# Scheda_ufficiale_2020_team_SPQR_3.net
KiCad netlist of a schematic drawn in EAGLE
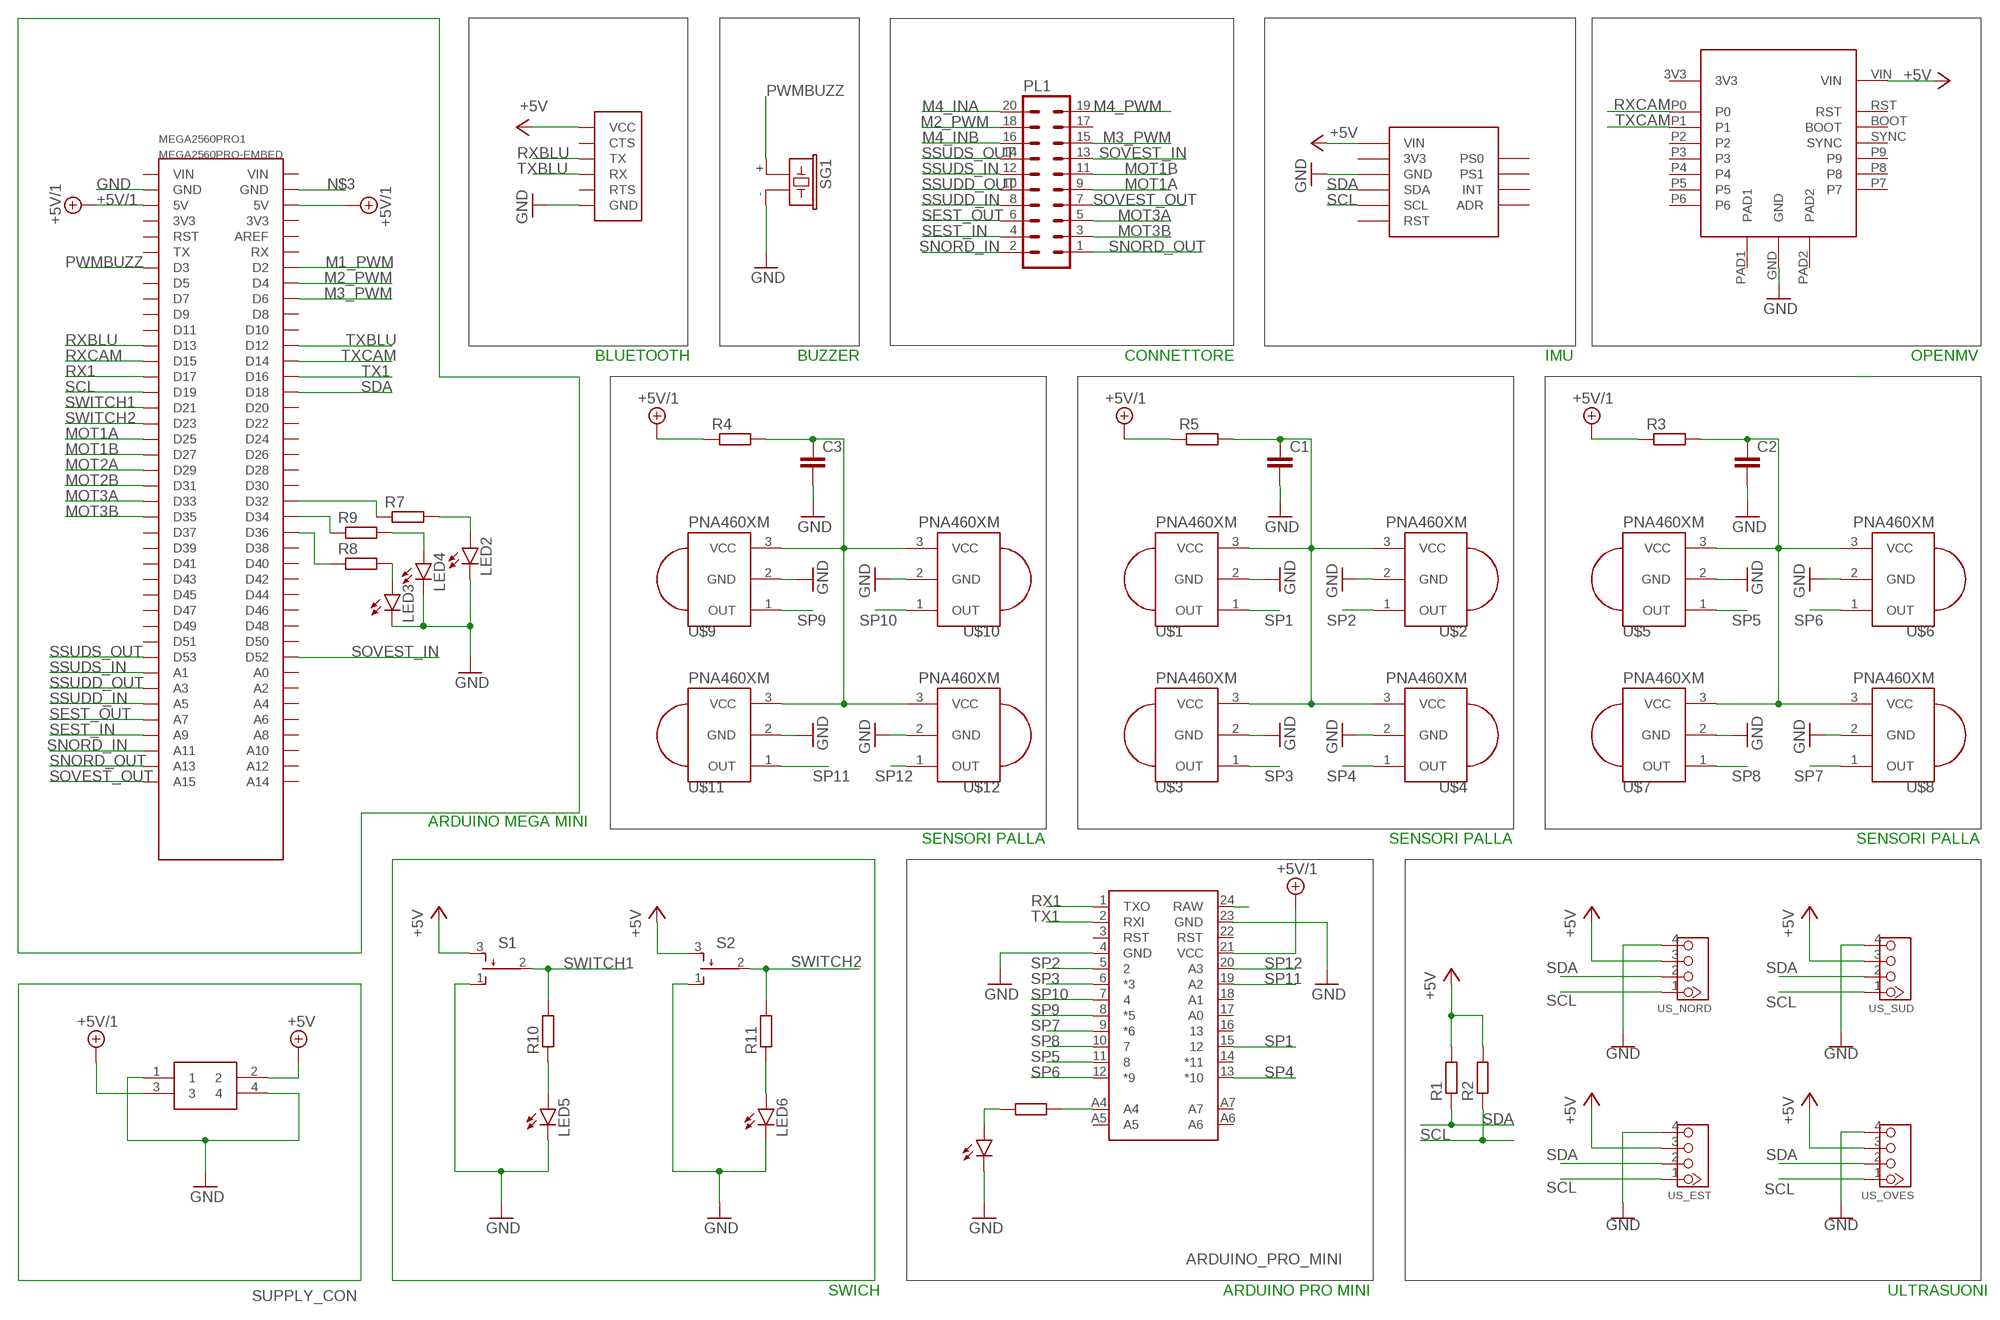
[diagram p0: schematic, sheet 1]

(export (version "E")
  (design (tool "Eeschema 10.0.6"))
  (components
    (comp (ref "ARDUINO_PRO_MINI")
      (value "ARDUINO_PRO_MINI")
      (footprint "eagle-import:ARDUINO_PRO_MINI")
      (libsource (lib "eagle-import") (part "ARDUINO_PRO_MINI"))
    )
    (comp (ref "C1")
      (value "C-EUC0805")
      (footprint "eagle-import:C0805")
      (libsource (lib "eagle-import") (part "C-EUC0805"))
    )
    (comp (ref "C2")
      (value "C-EUC0805")
      (footprint "eagle-import:C0805")
      (libsource (lib "eagle-import") (part "C-EUC0805"))
    )
    (comp (ref "C3")
      (value "C-EUC0805")
      (footprint "eagle-import:C0805")
      (libsource (lib "eagle-import") (part "C-EUC0805"))
    )
    (comp (ref "LED1")
      (value "LEDCHIPLED_1206")
      (footprint "eagle-import:CHIPLED_1206")
      (libsource (lib "eagle-import") (part "LEDCHIPLED_1206"))
    )
    (comp (ref "LED2")
      (value "LEDCHIPLED_1206")
      (footprint "eagle-import:CHIPLED_1206")
      (libsource (lib "eagle-import") (part "LEDCHIPLED_1206"))
    )
    (comp (ref "LED3")
      (value "LEDCHIPLED_1206")
      (footprint "eagle-import:CHIPLED_1206")
      (libsource (lib "eagle-import") (part "LEDCHIPLED_1206"))
    )
    (comp (ref "LED4")
      (value "LEDCHIPLED_1206")
      (footprint "eagle-import:CHIPLED_1206")
      (libsource (lib "eagle-import") (part "LEDCHIPLED_1206"))
    )
    (comp (ref "LED5")
      (value "LEDCHIPLED_1206")
      (footprint "eagle-import:CHIPLED_1206")
      (libsource (lib "eagle-import") (part "LEDCHIPLED_1206"))
    )
    (comp (ref "LED6")
      (value "LEDCHIPLED_1206")
      (footprint "eagle-import:CHIPLED_1206")
      (libsource (lib "eagle-import") (part "LEDCHIPLED_1206"))
    )
    (comp (ref "MEGA2560PRO1")
      (value "MEGA2560PRO-EMBED")
      (footprint "eagle-import:MEGA2560PRO-EMBED")
      (libsource (lib "eagle-import") (part "MEGA2560PRO-EMBED"))
    )
    (comp (ref "PL1")
      (value "20V")
      (footprint "eagle-import:20V")
      (libsource (lib "eagle-import") (part "20V"))
    )
    (comp (ref "R1")
      (value "R-EU_R0805")
      (footprint "eagle-import:R0805")
      (libsource (lib "eagle-import") (part "R-EU_R0805"))
    )
    (comp (ref "R2")
      (value "R-EU_R0805")
      (footprint "eagle-import:R0805")
      (libsource (lib "eagle-import") (part "R-EU_R0805"))
    )
    (comp (ref "R3")
      (value "R-EU_R0805")
      (footprint "eagle-import:R0805")
      (libsource (lib "eagle-import") (part "R-EU_R0805"))
    )
    (comp (ref "R4")
      (value "R-EU_R0805")
      (footprint "eagle-import:R0805")
      (libsource (lib "eagle-import") (part "R-EU_R0805"))
    )
    (comp (ref "R5")
      (value "R-EU_R0805")
      (footprint "eagle-import:R0805")
      (libsource (lib "eagle-import") (part "R-EU_R0805"))
    )
    (comp (ref "R6")
      (value "R-EU_R0805")
      (footprint "eagle-import:R0805")
      (libsource (lib "eagle-import") (part "R-EU_R0805"))
    )
    (comp (ref "R7")
      (value "R-EU_R0805")
      (footprint "eagle-import:R0805")
      (libsource (lib "eagle-import") (part "R-EU_R0805"))
    )
    (comp (ref "R8")
      (value "R-EU_R0805")
      (footprint "eagle-import:R0805")
      (libsource (lib "eagle-import") (part "R-EU_R0805"))
    )
    (comp (ref "R9")
      (value "R-EU_R0805")
      (footprint "eagle-import:R0805")
      (libsource (lib "eagle-import") (part "R-EU_R0805"))
    )
    (comp (ref "R10")
      (value "R-EU_R0805")
      (footprint "eagle-import:R0805")
      (libsource (lib "eagle-import") (part "R-EU_R0805"))
    )
    (comp (ref "R11")
      (value "R-EU_R0805")
      (footprint "eagle-import:R0805")
      (libsource (lib "eagle-import") (part "R-EU_R0805"))
    )
    (comp (ref "S1")
      (value "TL38PO")
      (footprint "eagle-import:TL3XPO")
      (libsource (lib "eagle-import") (part "TL38PO"))
    )
    (comp (ref "S2")
      (value "TL38PO")
      (footprint "eagle-import:TL3XPO")
      (libsource (lib "eagle-import") (part "TL38PO"))
    )
    (comp (ref "SG1")
      (value "F/CM12P")
      (footprint "eagle-import:F_CM12P")
      (libsource (lib "eagle-import") (part "F/CM12P"))
    )
    (comp (ref "SUPPLY_CON")
      (value "39-28-1043")
      (footprint "eagle-import:39-28-1043")
      (fields (field (name "MOUSER_PART_NUMBER") "538-39-28-1043") (field (name "RS_PART_NUMBER") "4841899P"))
      (libsource (lib "eagle-import") (part "39-28-1043"))
    )
    (comp (ref "U$1")
      (value "PNA460XM")
      (footprint "eagle-import:PNA460XM")
      (libsource (lib "eagle-import") (part "PNA460XM"))
    )
    (comp (ref "U$2")
      (value "PNA460XM")
      (footprint "eagle-import:PNA460XM")
      (libsource (lib "eagle-import") (part "PNA460XM"))
    )
    (comp (ref "U$3")
      (value "PNA460XM")
      (footprint "eagle-import:PNA460XM")
      (libsource (lib "eagle-import") (part "PNA460XM"))
    )
    (comp (ref "U$4")
      (value "PNA460XM")
      (footprint "eagle-import:PNA460XM")
      (libsource (lib "eagle-import") (part "PNA460XM"))
    )
    (comp (ref "U$5")
      (value "PNA460XM")
      (footprint "eagle-import:PNA460XM")
      (libsource (lib "eagle-import") (part "PNA460XM"))
    )
    (comp (ref "U$6")
      (value "PNA460XM")
      (footprint "eagle-import:PNA460XM")
      (libsource (lib "eagle-import") (part "PNA460XM"))
    )
    (comp (ref "U$7")
      (value "PNA460XM")
      (footprint "eagle-import:PNA460XM")
      (libsource (lib "eagle-import") (part "PNA460XM"))
    )
    (comp (ref "U$8")
      (value "PNA460XM")
      (footprint "eagle-import:PNA460XM")
      (libsource (lib "eagle-import") (part "PNA460XM"))
    )
    (comp (ref "U$9")
      (value "PNA460XM")
      (footprint "eagle-import:PNA460XM")
      (libsource (lib "eagle-import") (part "PNA460XM"))
    )
    (comp (ref "U$10")
      (value "PNA460XM")
      (footprint "eagle-import:PNA460XM")
      (libsource (lib "eagle-import") (part "PNA460XM"))
    )
    (comp (ref "U$11")
      (value "PNA460XM")
      (footprint "eagle-import:PNA460XM")
      (libsource (lib "eagle-import") (part "PNA460XM"))
    )
    (comp (ref "U$12")
      (value "PNA460XM")
      (footprint "eagle-import:PNA460XM")
      (libsource (lib "eagle-import") (part "PNA460XM"))
    )
    (comp (ref "U$14")
      (value "BLUESMIRF")
      (footprint "eagle-import:BLUESMIRF")
      (libsource (lib "eagle-import") (part "BLUESMIRF"))
    )
    (comp (ref "U$16")
      (value "BNO055")
      (footprint "eagle-import:BNO055")
      (libsource (lib "eagle-import") (part "BNO055"))
    )
    (comp (ref "U$17")
      (value "OPENMV_H7")
      (footprint "eagle-import:OPENMV_H7")
      (libsource (lib "eagle-import") (part "OPENMV_H7"))
    )
    (comp (ref "US_EST")
      (value "TWIG_2.0")
      (footprint "eagle-import:2.0_1X4")
      (libsource (lib "eagle-import") (part "TWIG_2.0"))
    )
    (comp (ref "US_NORD")
      (value "TWIG_2.0")
      (footprint "eagle-import:2.0_1X4")
      (libsource (lib "eagle-import") (part "TWIG_2.0"))
    )
    (comp (ref "US_OVES")
      (value "TWIG_2.0")
      (footprint "eagle-import:2.0_1X4")
      (libsource (lib "eagle-import") (part "TWIG_2.0"))
    )
    (comp (ref "US_SUD")
      (value "TWIG_2.0")
      (footprint "eagle-import:2.0_1X4")
      (libsource (lib "eagle-import") (part "TWIG_2.0"))
    )
  )
  (nets
    (net (code "1") (name "+5V") (class "Default")
      (node (ref "R1") (pin "2") (pinfunction "2_2") (pintype "passive"))
      (node (ref "R2") (pin "2") (pinfunction "2_2") (pintype "passive"))
      (node (ref "S1") (pin "3") (pinfunction "S_3") (pintype "passive"))
      (node (ref "S2") (pin "3") (pinfunction "S_3") (pintype "passive"))
      (node (ref "SUPPLY_CON") (pin "2") (pinfunction "2_2") (pintype "bidirectional"))
      (node (ref "U$14") (pin "VCC") (pinfunction "VCC_VCC") (pintype "bidirectional"))
      (node (ref "U$16") (pin "VIN") (pinfunction "VIN_VIN") (pintype "bidirectional"))
      (node (ref "U$17") (pin "VIN") (pinfunction "VIN_VIN") (pintype "bidirectional"))
      (node (ref "US_EST") (pin "3") (pinfunction "3_3") (pintype "bidirectional"))
      (node (ref "US_NORD") (pin "3") (pinfunction "3_3") (pintype "bidirectional"))
      (node (ref "US_OVES") (pin "3") (pinfunction "3_3") (pintype "bidirectional"))
      (node (ref "US_SUD") (pin "3") (pinfunction "3_3") (pintype "bidirectional"))
    )
    (net (code "2") (name "+5V{slash}1") (class "Default")
      (node (ref "ARDUINO_PRO_MINI") (pin "21") (pinfunction "VCC_21") (pintype "power_in"))
      (node (ref "MEGA2560PRO1") (pin "5V@1") (pinfunction "5V_5V@1") (pintype "bidirectional"))
      (node (ref "MEGA2560PRO1") (pin "5V@2") (pinfunction "5V_5V@2") (pintype "bidirectional"))
      (node (ref "R3") (pin "1") (pinfunction "1_1") (pintype "passive"))
      (node (ref "R4") (pin "1") (pinfunction "1_1") (pintype "passive"))
      (node (ref "R5") (pin "1") (pinfunction "1_1") (pintype "passive"))
      (node (ref "SUPPLY_CON") (pin "3") (pinfunction "3_3") (pintype "bidirectional"))
    )
    (net (code "3") (name "/M1_PWM") (class "Default")
      (node (ref "MEGA2560PRO1") (pin "D2") (pinfunction "D2_D2") (pintype "bidirectional"))
    )
    (net (code "4") (name "/M2_PWM") (class "Default")
      (node (ref "MEGA2560PRO1") (pin "D4") (pinfunction "D4_D4") (pintype "bidirectional"))
      (node (ref "PL1") (pin "18") (pinfunction "18_18") (pintype "passive"))
    )
    (net (code "5") (name "/M3_PWM") (class "Default")
      (node (ref "MEGA2560PRO1") (pin "D6") (pinfunction "D6_D6") (pintype "bidirectional"))
      (node (ref "PL1") (pin "15") (pinfunction "15_15") (pintype "passive"))
    )
    (net (code "6") (name "/M4_INA") (class "Default")
      (node (ref "PL1") (pin "20") (pinfunction "20_20") (pintype "passive"))
    )
    (net (code "7") (name "/M4_INB") (class "Default")
      (node (ref "PL1") (pin "16") (pinfunction "16_16") (pintype "passive"))
    )
    (net (code "8") (name "/M4_PWM") (class "Default")
      (node (ref "PL1") (pin "19") (pinfunction "19_19") (pintype "passive"))
    )
    (net (code "9") (name "/MOT1A") (class "Default")
      (node (ref "MEGA2560PRO1") (pin "D25") (pinfunction "D25_D25") (pintype "bidirectional"))
      (node (ref "PL1") (pin "9") (pinfunction "9_9") (pintype "passive"))
    )
    (net (code "10") (name "/MOT1B") (class "Default")
      (node (ref "MEGA2560PRO1") (pin "D27") (pinfunction "D27_D27") (pintype "bidirectional"))
      (node (ref "PL1") (pin "11") (pinfunction "11_11") (pintype "passive"))
    )
    (net (code "11") (name "/MOT2A") (class "Default")
      (node (ref "MEGA2560PRO1") (pin "D29") (pinfunction "D29_D29") (pintype "bidirectional"))
    )
    (net (code "12") (name "/MOT2B") (class "Default")
      (node (ref "MEGA2560PRO1") (pin "D31") (pinfunction "D31_D31") (pintype "bidirectional"))
    )
    (net (code "13") (name "/MOT3A") (class "Default")
      (node (ref "MEGA2560PRO1") (pin "D33") (pinfunction "D33_D33") (pintype "bidirectional"))
      (node (ref "PL1") (pin "5") (pinfunction "5_5") (pintype "passive"))
    )
    (net (code "14") (name "/MOT3B") (class "Default")
      (node (ref "MEGA2560PRO1") (pin "D35") (pinfunction "D35_D35") (pintype "bidirectional"))
      (node (ref "PL1") (pin "3") (pinfunction "3_3") (pintype "passive"))
    )
    (net (code "15") (name "/N$3") (class "Default")
      (node (ref "MEGA2560PRO1") (pin "GND@2") (pinfunction "GND_GND@2") (pintype "bidirectional"))
    )
    (net (code "16") (name "/PWMBUZZ") (class "Default")
      (node (ref "MEGA2560PRO1") (pin "D3") (pinfunction "D3_D3") (pintype "bidirectional"))
      (node (ref "SG1") (pin "+") (pinfunction "1_+") (pintype "passive"))
    )
    (net (code "17") (name "/RX1") (class "Default")
      (node (ref "ARDUINO_PRO_MINI") (pin "1") (pinfunction "TXO_1") (pintype "bidirectional"))
      (node (ref "MEGA2560PRO1") (pin "D17") (pinfunction "D17_D17") (pintype "bidirectional"))
    )
    (net (code "18") (name "/RXBLU") (class "Default")
      (node (ref "MEGA2560PRO1") (pin "D13") (pinfunction "D13_D13") (pintype "bidirectional"))
      (node (ref "U$14") (pin "TX") (pinfunction "TX_TX") (pintype "bidirectional"))
    )
    (net (code "19") (name "/RXCAM") (class "Default")
      (node (ref "MEGA2560PRO1") (pin "D15") (pinfunction "D15_D15") (pintype "bidirectional"))
      (node (ref "U$17") (pin "P0") (pinfunction "P0_P0") (pintype "bidirectional"))
    )
    (net (code "20") (name "/SCL") (class "Default")
      (node (ref "MEGA2560PRO1") (pin "D19") (pinfunction "D19_D19") (pintype "bidirectional"))
      (node (ref "R2") (pin "1") (pinfunction "1_1") (pintype "passive"))
      (node (ref "U$16") (pin "SCL") (pinfunction "SCL_SCL") (pintype "bidirectional"))
      (node (ref "US_EST") (pin "1") (pinfunction "1_1") (pintype "bidirectional"))
      (node (ref "US_NORD") (pin "1") (pinfunction "1_1") (pintype "bidirectional"))
      (node (ref "US_OVES") (pin "1") (pinfunction "1_1") (pintype "bidirectional"))
      (node (ref "US_SUD") (pin "1") (pinfunction "1_1") (pintype "bidirectional"))
    )
    (net (code "21") (name "/SDA") (class "Default")
      (node (ref "MEGA2560PRO1") (pin "D18") (pinfunction "D18_D18") (pintype "bidirectional"))
      (node (ref "R1") (pin "1") (pinfunction "1_1") (pintype "passive"))
      (node (ref "U$16") (pin "SDA") (pinfunction "SDA_SDA") (pintype "bidirectional"))
      (node (ref "US_EST") (pin "2") (pinfunction "2_2") (pintype "bidirectional"))
      (node (ref "US_NORD") (pin "2") (pinfunction "2_2") (pintype "bidirectional"))
      (node (ref "US_OVES") (pin "2") (pinfunction "2_2") (pintype "bidirectional"))
      (node (ref "US_SUD") (pin "2") (pinfunction "2_2") (pintype "bidirectional"))
    )
    (net (code "22") (name "/SEST_IN") (class "Default")
      (node (ref "MEGA2560PRO1") (pin "A9") (pinfunction "A9_A9") (pintype "bidirectional"))
      (node (ref "PL1") (pin "4") (pinfunction "4_4") (pintype "passive"))
    )
    (net (code "23") (name "/SEST_OUT") (class "Default")
      (node (ref "MEGA2560PRO1") (pin "A7") (pinfunction "A7_A7") (pintype "bidirectional"))
      (node (ref "PL1") (pin "6") (pinfunction "6_6") (pintype "passive"))
    )
    (net (code "24") (name "/SNORD_IN") (class "Default")
      (node (ref "MEGA2560PRO1") (pin "A11") (pinfunction "A11_A11") (pintype "bidirectional"))
      (node (ref "PL1") (pin "2") (pinfunction "2_2") (pintype "passive"))
    )
    (net (code "25") (name "/SNORD_OUT") (class "Default")
      (node (ref "MEGA2560PRO1") (pin "A13") (pinfunction "A13_A13") (pintype "bidirectional"))
      (node (ref "PL1") (pin "1") (pinfunction "1_1") (pintype "passive"))
    )
    (net (code "26") (name "/SOVEST_IN") (class "Default")
      (node (ref "MEGA2560PRO1") (pin "D52") (pinfunction "D52_D52") (pintype "bidirectional"))
      (node (ref "PL1") (pin "13") (pinfunction "13_13") (pintype "passive"))
    )
    (net (code "27") (name "/SOVEST_OUT") (class "Default")
      (node (ref "MEGA2560PRO1") (pin "A15") (pinfunction "A15_A15") (pintype "bidirectional"))
      (node (ref "PL1") (pin "7") (pinfunction "7_7") (pintype "passive"))
    )
    (net (code "28") (name "/SP1") (class "Default")
      (node (ref "ARDUINO_PRO_MINI") (pin "15") (pinfunction "12_15") (pintype "bidirectional"))
      (node (ref "U$1") (pin "1") (pinfunction "OUT_1") (pintype "output"))
    )
    (net (code "29") (name "/SP2") (class "Default")
      (node (ref "ARDUINO_PRO_MINI") (pin "5") (pinfunction "2_5") (pintype "bidirectional"))
      (node (ref "U$2") (pin "1") (pinfunction "OUT_1") (pintype "output"))
    )
    (net (code "30") (name "/SP3") (class "Default")
      (node (ref "ARDUINO_PRO_MINI") (pin "6") (pinfunction "*3_6") (pintype "bidirectional"))
      (node (ref "U$3") (pin "1") (pinfunction "OUT_1") (pintype "output"))
    )
    (net (code "31") (name "/SP4") (class "Default")
      (node (ref "ARDUINO_PRO_MINI") (pin "13") (pinfunction "*10_13") (pintype "bidirectional"))
      (node (ref "U$4") (pin "1") (pinfunction "OUT_1") (pintype "output"))
    )
    (net (code "32") (name "/SP5") (class "Default")
      (node (ref "ARDUINO_PRO_MINI") (pin "11") (pinfunction "8_11") (pintype "bidirectional"))
      (node (ref "U$5") (pin "1") (pinfunction "OUT_1") (pintype "output"))
    )
    (net (code "33") (name "/SP6") (class "Default")
      (node (ref "ARDUINO_PRO_MINI") (pin "12") (pinfunction "*9_12") (pintype "bidirectional"))
      (node (ref "U$6") (pin "1") (pinfunction "OUT_1") (pintype "output"))
    )
    (net (code "34") (name "/SP7") (class "Default")
      (node (ref "ARDUINO_PRO_MINI") (pin "9") (pinfunction "*6_9") (pintype "bidirectional"))
      (node (ref "U$8") (pin "1") (pinfunction "OUT_1") (pintype "output"))
    )
    (net (code "35") (name "/SP8") (class "Default")
      (node (ref "ARDUINO_PRO_MINI") (pin "10") (pinfunction "7_10") (pintype "bidirectional"))
      (node (ref "U$7") (pin "1") (pinfunction "OUT_1") (pintype "output"))
    )
    (net (code "36") (name "/SP9") (class "Default")
      (node (ref "ARDUINO_PRO_MINI") (pin "8") (pinfunction "*5_8") (pintype "bidirectional"))
      (node (ref "U$9") (pin "1") (pinfunction "OUT_1") (pintype "output"))
    )
    (net (code "37") (name "/SP10") (class "Default")
      (node (ref "ARDUINO_PRO_MINI") (pin "7") (pinfunction "4_7") (pintype "bidirectional"))
      (node (ref "U$10") (pin "1") (pinfunction "OUT_1") (pintype "output"))
    )
    (net (code "38") (name "/SP11") (class "Default")
      (node (ref "ARDUINO_PRO_MINI") (pin "19") (pinfunction "A2_19") (pintype "bidirectional"))
      (node (ref "U$11") (pin "1") (pinfunction "OUT_1") (pintype "output"))
    )
    (net (code "39") (name "/SP12") (class "Default")
      (node (ref "ARDUINO_PRO_MINI") (pin "20") (pinfunction "A3_20") (pintype "bidirectional"))
      (node (ref "U$12") (pin "1") (pinfunction "OUT_1") (pintype "output"))
    )
    (net (code "40") (name "/SSUDD_IN") (class "Default")
      (node (ref "MEGA2560PRO1") (pin "A5") (pinfunction "A5_A5") (pintype "bidirectional"))
      (node (ref "PL1") (pin "8") (pinfunction "8_8") (pintype "passive"))
    )
    (net (code "41") (name "/SSUDD_OUT") (class "Default")
      (node (ref "MEGA2560PRO1") (pin "A3") (pinfunction "A3_A3") (pintype "bidirectional"))
      (node (ref "PL1") (pin "10") (pinfunction "10_10") (pintype "passive"))
    )
    (net (code "42") (name "/SSUDS_IN") (class "Default")
      (node (ref "MEGA2560PRO1") (pin "A1") (pinfunction "A1_A1") (pintype "bidirectional"))
      (node (ref "PL1") (pin "12") (pinfunction "12_12") (pintype "passive"))
    )
    (net (code "43") (name "/SSUDS_OUT") (class "Default")
      (node (ref "MEGA2560PRO1") (pin "D53") (pinfunction "D53_D53") (pintype "bidirectional"))
      (node (ref "PL1") (pin "14") (pinfunction "14_14") (pintype "passive"))
    )
    (net (code "44") (name "/SWITCH1") (class "Default")
      (node (ref "MEGA2560PRO1") (pin "D21") (pinfunction "D21_D21") (pintype "bidirectional"))
      (node (ref "R10") (pin "2") (pinfunction "2_2") (pintype "passive"))
      (node (ref "S1") (pin "2") (pinfunction "P_2") (pintype "passive"))
    )
    (net (code "45") (name "/SWITCH2") (class "Default")
      (node (ref "MEGA2560PRO1") (pin "D23") (pinfunction "D23_D23") (pintype "bidirectional"))
      (node (ref "R11") (pin "2") (pinfunction "2_2") (pintype "passive"))
      (node (ref "S2") (pin "2") (pinfunction "P_2") (pintype "passive"))
    )
    (net (code "46") (name "/TX1") (class "Default")
      (node (ref "ARDUINO_PRO_MINI") (pin "2") (pinfunction "RXI_2") (pintype "bidirectional"))
      (node (ref "MEGA2560PRO1") (pin "D16") (pinfunction "D16_D16") (pintype "bidirectional"))
    )
    (net (code "47") (name "/TXBLU") (class "Default")
      (node (ref "MEGA2560PRO1") (pin "D12") (pinfunction "D12_D12") (pintype "bidirectional"))
      (node (ref "U$14") (pin "RX") (pinfunction "RX_RX") (pintype "bidirectional"))
    )
    (net (code "48") (name "/TXCAM") (class "Default")
      (node (ref "MEGA2560PRO1") (pin "D14") (pinfunction "D14_D14") (pintype "bidirectional"))
      (node (ref "U$17") (pin "P1") (pinfunction "P1_P1") (pintype "bidirectional"))
    )
    (net (code "49") (name "GND") (class "Default")
      (node (ref "ARDUINO_PRO_MINI") (pin "23") (pinfunction "GND_23") (pintype "power_in"))
      (node (ref "ARDUINO_PRO_MINI") (pin "4") (pinfunction "GND_4") (pintype "power_in"))
      (node (ref "C1") (pin "2") (pinfunction "2_2") (pintype "passive"))
      (node (ref "C2") (pin "2") (pinfunction "2_2") (pintype "passive"))
      (node (ref "C3") (pin "2") (pinfunction "2_2") (pintype "passive"))
      (node (ref "LED1") (pin "C") (pinfunction "C_C") (pintype "passive"))
      (node (ref "LED2") (pin "C") (pinfunction "C_C") (pintype "passive"))
      (node (ref "LED3") (pin "C") (pinfunction "C_C") (pintype "passive"))
      (node (ref "LED4") (pin "C") (pinfunction "C_C") (pintype "passive"))
      (node (ref "LED5") (pin "C") (pinfunction "C_C") (pintype "passive"))
      (node (ref "LED6") (pin "C") (pinfunction "C_C") (pintype "passive"))
      (node (ref "MEGA2560PRO1") (pin "GND@1") (pinfunction "GND_GND@1") (pintype "bidirectional"))
      (node (ref "S1") (pin "1") (pinfunction "O_1") (pintype "passive"))
      (node (ref "S2") (pin "1") (pinfunction "O_1") (pintype "passive"))
      (node (ref "SG1") (pin "-") (pinfunction "2_-") (pintype "passive"))
      (node (ref "SUPPLY_CON") (pin "1") (pinfunction "1_1") (pintype "bidirectional"))
      (node (ref "SUPPLY_CON") (pin "4") (pinfunction "4_4") (pintype "bidirectional"))
      (node (ref "U$1") (pin "2") (pinfunction "GND_2") (pintype "power_in"))
      (node (ref "U$10") (pin "2") (pinfunction "GND_2") (pintype "power_in"))
      (node (ref "U$11") (pin "2") (pinfunction "GND_2") (pintype "power_in"))
      (node (ref "U$12") (pin "2") (pinfunction "GND_2") (pintype "power_in"))
      (node (ref "U$14") (pin "GND") (pinfunction "GND_GND") (pintype "bidirectional"))
      (node (ref "U$16") (pin "GND") (pinfunction "GND_GND") (pintype "bidirectional"))
      (node (ref "U$17") (pin "GND") (pinfunction "GND_GND") (pintype "bidirectional"))
      (node (ref "U$2") (pin "2") (pinfunction "GND_2") (pintype "power_in"))
      (node (ref "U$3") (pin "2") (pinfunction "GND_2") (pintype "power_in"))
      (node (ref "U$4") (pin "2") (pinfunction "GND_2") (pintype "power_in"))
      (node (ref "U$5") (pin "2") (pinfunction "GND_2") (pintype "power_in"))
      (node (ref "U$6") (pin "2") (pinfunction "GND_2") (pintype "power_in"))
      (node (ref "U$7") (pin "2") (pinfunction "GND_2") (pintype "power_in"))
      (node (ref "U$8") (pin "2") (pinfunction "GND_2") (pintype "power_in"))
      (node (ref "U$9") (pin "2") (pinfunction "GND_2") (pintype "power_in"))
      (node (ref "US_EST") (pin "4") (pinfunction "4_4") (pintype "bidirectional"))
      (node (ref "US_NORD") (pin "4") (pinfunction "4_4") (pintype "bidirectional"))
      (node (ref "US_OVES") (pin "4") (pinfunction "4_4") (pintype "bidirectional"))
      (node (ref "US_SUD") (pin "4") (pinfunction "4_4") (pintype "bidirectional"))
    )
    (net (code "50") (name "Net-(ARDUINO_PRO_MINI-PadA4)") (class "Default")
      (node (ref "ARDUINO_PRO_MINI") (pin "A4") (pinfunction "A4_A4") (pintype "bidirectional"))
      (node (ref "R6") (pin "2") (pinfunction "2_2") (pintype "passive"))
    )
    (net (code "51") (name "Net-(LED1-PadA)") (class "Default")
      (node (ref "LED1") (pin "A") (pinfunction "A_A") (pintype "passive"))
      (node (ref "R6") (pin "1") (pinfunction "1_1") (pintype "passive"))
    )
    (net (code "52") (name "Net-(LED2-PadA)") (class "Default")
      (node (ref "LED2") (pin "A") (pinfunction "A_A") (pintype "passive"))
      (node (ref "R7") (pin "2") (pinfunction "2_2") (pintype "passive"))
    )
    (net (code "53") (name "Net-(LED3-PadA)") (class "Default")
      (node (ref "LED3") (pin "A") (pinfunction "A_A") (pintype "passive"))
      (node (ref "R8") (pin "2") (pinfunction "2_2") (pintype "passive"))
    )
    (net (code "54") (name "Net-(LED4-PadA)") (class "Default")
      (node (ref "LED4") (pin "A") (pinfunction "A_A") (pintype "passive"))
      (node (ref "R9") (pin "2") (pinfunction "2_2") (pintype "passive"))
    )
    (net (code "55") (name "Net-(LED5-PadA)") (class "Default")
      (node (ref "LED5") (pin "A") (pinfunction "A_A") (pintype "passive"))
      (node (ref "R10") (pin "1") (pinfunction "1_1") (pintype "passive"))
    )
    (net (code "56") (name "Net-(LED6-PadA)") (class "Default")
      (node (ref "LED6") (pin "A") (pinfunction "A_A") (pintype "passive"))
      (node (ref "R11") (pin "1") (pinfunction "1_1") (pintype "passive"))
    )
    (net (code "57") (name "Net-(MEGA2560PRO1-PadD32)") (class "Default")
      (node (ref "MEGA2560PRO1") (pin "D32") (pinfunction "D32_D32") (pintype "bidirectional"))
      (node (ref "R7") (pin "1") (pinfunction "1_1") (pintype "passive"))
    )
    (net (code "58") (name "Net-(MEGA2560PRO1-PadD34)") (class "Default")
      (node (ref "MEGA2560PRO1") (pin "D34") (pinfunction "D34_D34") (pintype "bidirectional"))
      (node (ref "R9") (pin "1") (pinfunction "1_1") (pintype "passive"))
    )
    (net (code "59") (name "Net-(MEGA2560PRO1-PadD36)") (class "Default")
      (node (ref "MEGA2560PRO1") (pin "D36") (pinfunction "D36_D36") (pintype "bidirectional"))
      (node (ref "R8") (pin "1") (pinfunction "1_1") (pintype "passive"))
    )
    (net (code "60") (name "Net-(U$1-VCC)") (class "Default")
      (node (ref "C1") (pin "1") (pinfunction "1_1") (pintype "passive"))
      (node (ref "R5") (pin "2") (pinfunction "2_2") (pintype "passive"))
      (node (ref "U$1") (pin "3") (pinfunction "VCC_3") (pintype "power_in"))
      (node (ref "U$2") (pin "3") (pinfunction "VCC_3") (pintype "power_in"))
      (node (ref "U$3") (pin "3") (pinfunction "VCC_3") (pintype "power_in"))
      (node (ref "U$4") (pin "3") (pinfunction "VCC_3") (pintype "power_in"))
    )
    (net (code "61") (name "Net-(U$5-VCC)") (class "Default")
      (node (ref "C2") (pin "1") (pinfunction "1_1") (pintype "passive"))
      (node (ref "R3") (pin "2") (pinfunction "2_2") (pintype "passive"))
      (node (ref "U$5") (pin "3") (pinfunction "VCC_3") (pintype "power_in"))
      (node (ref "U$6") (pin "3") (pinfunction "VCC_3") (pintype "power_in"))
      (node (ref "U$7") (pin "3") (pinfunction "VCC_3") (pintype "power_in"))
      (node (ref "U$8") (pin "3") (pinfunction "VCC_3") (pintype "power_in"))
    )
    (net (code "62") (name "Net-(U$10-VCC)") (class "Default")
      (node (ref "C3") (pin "1") (pinfunction "1_1") (pintype "passive"))
      (node (ref "R4") (pin "2") (pinfunction "2_2") (pintype "passive"))
      (node (ref "U$10") (pin "3") (pinfunction "VCC_3") (pintype "power_in"))
      (node (ref "U$11") (pin "3") (pinfunction "VCC_3") (pintype "power_in"))
      (node (ref "U$12") (pin "3") (pinfunction "VCC_3") (pintype "power_in"))
      (node (ref "U$9") (pin "3") (pinfunction "VCC_3") (pintype "power_in"))
    )
    (net (code "63") (name "unconnected-(ARDUINO_PRO_MINI-*11-Pad14)") (class "Default")
      (node (ref "ARDUINO_PRO_MINI") (pin "14") (pinfunction "*11_14") (pintype "bidirectional"))
    )
    (net (code "64") (name "unconnected-(ARDUINO_PRO_MINI-13-Pad16)") (class "Default")
      (node (ref "ARDUINO_PRO_MINI") (pin "16") (pinfunction "13_16") (pintype "bidirectional"))
    )
    (net (code "65") (name "unconnected-(ARDUINO_PRO_MINI-A0-Pad17)") (class "Default")
      (node (ref "ARDUINO_PRO_MINI") (pin "17") (pinfunction "A0_17") (pintype "bidirectional"))
    )
    (net (code "66") (name "unconnected-(ARDUINO_PRO_MINI-A1-Pad18)") (class "Default")
      (node (ref "ARDUINO_PRO_MINI") (pin "18") (pinfunction "A1_18") (pintype "bidirectional"))
    )
    (net (code "67") (name "unconnected-(ARDUINO_PRO_MINI-PadA5)") (class "Default")
      (node (ref "ARDUINO_PRO_MINI") (pin "A5") (pinfunction "A5_A5") (pintype "bidirectional"))
    )
    (net (code "68") (name "unconnected-(ARDUINO_PRO_MINI-PadA6)") (class "Default")
      (node (ref "ARDUINO_PRO_MINI") (pin "A6") (pinfunction "A6_A6") (pintype "bidirectional"))
    )
    (net (code "69") (name "unconnected-(ARDUINO_PRO_MINI-PadA7)") (class "Default")
      (node (ref "ARDUINO_PRO_MINI") (pin "A7") (pinfunction "A7_A7") (pintype "bidirectional"))
    )
    (net (code "70") (name "unconnected-(ARDUINO_PRO_MINI-RAW-Pad24)") (class "Default")
      (node (ref "ARDUINO_PRO_MINI") (pin "24") (pinfunction "RAW_24") (pintype "power_in"))
    )
    (net (code "71") (name "unconnected-(ARDUINO_PRO_MINI-RST-Pad3)") (class "Default")
      (node (ref "ARDUINO_PRO_MINI") (pin "3") (pinfunction "RST_3") (pintype "bidirectional"))
    )
    (net (code "72") (name "unconnected-(ARDUINO_PRO_MINI-RST-Pad22)") (class "Default")
      (node (ref "ARDUINO_PRO_MINI") (pin "22") (pinfunction "RST_22") (pintype "bidirectional"))
    )
    (net (code "73") (name "unconnected-(MEGA2560PRO1-3V3-Pad3V3@1)") (class "Default")
      (node (ref "MEGA2560PRO1") (pin "3V3@1") (pinfunction "3V3_3V3@1") (pintype "bidirectional"))
    )
    (net (code "74") (name "unconnected-(MEGA2560PRO1-3V3-Pad3V3@2)") (class "Default")
      (node (ref "MEGA2560PRO1") (pin "3V3@2") (pinfunction "3V3_3V3@2") (pintype "bidirectional"))
    )
    (net (code "75") (name "unconnected-(MEGA2560PRO1-PadA0)") (class "Default")
      (node (ref "MEGA2560PRO1") (pin "A0") (pinfunction "A0_A0") (pintype "bidirectional"))
    )
    (net (code "76") (name "unconnected-(MEGA2560PRO1-PadA2)") (class "Default")
      (node (ref "MEGA2560PRO1") (pin "A2") (pinfunction "A2_A2") (pintype "bidirectional"))
    )
    (net (code "77") (name "unconnected-(MEGA2560PRO1-PadA4)") (class "Default")
      (node (ref "MEGA2560PRO1") (pin "A4") (pinfunction "A4_A4") (pintype "bidirectional"))
    )
    (net (code "78") (name "unconnected-(MEGA2560PRO1-PadA6)") (class "Default")
      (node (ref "MEGA2560PRO1") (pin "A6") (pinfunction "A6_A6") (pintype "bidirectional"))
    )
    (net (code "79") (name "unconnected-(MEGA2560PRO1-PadA8)") (class "Default")
      (node (ref "MEGA2560PRO1") (pin "A8") (pinfunction "A8_A8") (pintype "bidirectional"))
    )
    (net (code "80") (name "unconnected-(MEGA2560PRO1-PadA10)") (class "Default")
      (node (ref "MEGA2560PRO1") (pin "A10") (pinfunction "A10_A10") (pintype "bidirectional"))
    )
    (net (code "81") (name "unconnected-(MEGA2560PRO1-PadA12)") (class "Default")
      (node (ref "MEGA2560PRO1") (pin "A12") (pinfunction "A12_A12") (pintype "bidirectional"))
    )
    (net (code "82") (name "unconnected-(MEGA2560PRO1-PadA14)") (class "Default")
      (node (ref "MEGA2560PRO1") (pin "A14") (pinfunction "A14_A14") (pintype "bidirectional"))
    )
    (net (code "83") (name "unconnected-(MEGA2560PRO1-PadAREF)") (class "Default")
      (node (ref "MEGA2560PRO1") (pin "AREF") (pinfunction "AREF_AREF") (pintype "bidirectional"))
    )
    (net (code "84") (name "unconnected-(MEGA2560PRO1-PadD5)") (class "Default")
      (node (ref "MEGA2560PRO1") (pin "D5") (pinfunction "D5_D5") (pintype "bidirectional"))
    )
    (net (code "85") (name "unconnected-(MEGA2560PRO1-PadD7)") (class "Default")
      (node (ref "MEGA2560PRO1") (pin "D7") (pinfunction "D7_D7") (pintype "bidirectional"))
    )
    (net (code "86") (name "unconnected-(MEGA2560PRO1-PadD8)") (class "Default")
      (node (ref "MEGA2560PRO1") (pin "D8") (pinfunction "D8_D8") (pintype "bidirectional"))
    )
    (net (code "87") (name "unconnected-(MEGA2560PRO1-PadD9)") (class "Default")
      (node (ref "MEGA2560PRO1") (pin "D9") (pinfunction "D9_D9") (pintype "bidirectional"))
    )
    (net (code "88") (name "unconnected-(MEGA2560PRO1-PadD10)") (class "Default")
      (node (ref "MEGA2560PRO1") (pin "D10") (pinfunction "D10_D10") (pintype "bidirectional"))
    )
    (net (code "89") (name "unconnected-(MEGA2560PRO1-PadD11)") (class "Default")
      (node (ref "MEGA2560PRO1") (pin "D11") (pinfunction "D11_D11") (pintype "bidirectional"))
    )
    (net (code "90") (name "unconnected-(MEGA2560PRO1-PadD20)") (class "Default")
      (node (ref "MEGA2560PRO1") (pin "D20") (pinfunction "D20_D20") (pintype "bidirectional"))
    )
    (net (code "91") (name "unconnected-(MEGA2560PRO1-PadD22)") (class "Default")
      (node (ref "MEGA2560PRO1") (pin "D22") (pinfunction "D22_D22") (pintype "bidirectional"))
    )
    (net (code "92") (name "unconnected-(MEGA2560PRO1-PadD24)") (class "Default")
      (node (ref "MEGA2560PRO1") (pin "D24") (pinfunction "D24_D24") (pintype "bidirectional"))
    )
    (net (code "93") (name "unconnected-(MEGA2560PRO1-PadD26)") (class "Default")
      (node (ref "MEGA2560PRO1") (pin "D26") (pinfunction "D26_D26") (pintype "bidirectional"))
    )
    (net (code "94") (name "unconnected-(MEGA2560PRO1-PadD28)") (class "Default")
      (node (ref "MEGA2560PRO1") (pin "D28") (pinfunction "D28_D28") (pintype "bidirectional"))
    )
    (net (code "95") (name "unconnected-(MEGA2560PRO1-PadD30)") (class "Default")
      (node (ref "MEGA2560PRO1") (pin "D30") (pinfunction "D30_D30") (pintype "bidirectional"))
    )
    (net (code "96") (name "unconnected-(MEGA2560PRO1-PadD37)") (class "Default")
      (node (ref "MEGA2560PRO1") (pin "D37") (pinfunction "D37_D37") (pintype "bidirectional"))
    )
    (net (code "97") (name "unconnected-(MEGA2560PRO1-PadD38)") (class "Default")
      (node (ref "MEGA2560PRO1") (pin "D38") (pinfunction "D38_D38") (pintype "bidirectional"))
    )
    (net (code "98") (name "unconnected-(MEGA2560PRO1-PadD39)") (class "Default")
      (node (ref "MEGA2560PRO1") (pin "D39") (pinfunction "D39_D39") (pintype "bidirectional"))
    )
    (net (code "99") (name "unconnected-(MEGA2560PRO1-PadD40)") (class "Default")
      (node (ref "MEGA2560PRO1") (pin "D40") (pinfunction "D40_D40") (pintype "bidirectional"))
    )
    (net (code "100") (name "unconnected-(MEGA2560PRO1-PadD41)") (class "Default")
      (node (ref "MEGA2560PRO1") (pin "D41") (pinfunction "D41_D41") (pintype "bidirectional"))
    )
    (net (code "101") (name "unconnected-(MEGA2560PRO1-PadD42)") (class "Default")
      (node (ref "MEGA2560PRO1") (pin "D42") (pinfunction "D42_D42") (pintype "bidirectional"))
    )
    (net (code "102") (name "unconnected-(MEGA2560PRO1-PadD43)") (class "Default")
      (node (ref "MEGA2560PRO1") (pin "D43") (pinfunction "D43_D43") (pintype "bidirectional"))
    )
    (net (code "103") (name "unconnected-(MEGA2560PRO1-PadD44)") (class "Default")
      (node (ref "MEGA2560PRO1") (pin "D44") (pinfunction "D44_D44") (pintype "bidirectional"))
    )
    (net (code "104") (name "unconnected-(MEGA2560PRO1-PadD45)") (class "Default")
      (node (ref "MEGA2560PRO1") (pin "D45") (pinfunction "D45_D45") (pintype "bidirectional"))
    )
    (net (code "105") (name "unconnected-(MEGA2560PRO1-PadD46)") (class "Default")
      (node (ref "MEGA2560PRO1") (pin "D46") (pinfunction "D46_D46") (pintype "bidirectional"))
    )
    (net (code "106") (name "unconnected-(MEGA2560PRO1-PadD47)") (class "Default")
      (node (ref "MEGA2560PRO1") (pin "D47") (pinfunction "D47_D47") (pintype "bidirectional"))
    )
    (net (code "107") (name "unconnected-(MEGA2560PRO1-PadD48)") (class "Default")
      (node (ref "MEGA2560PRO1") (pin "D48") (pinfunction "D48_D48") (pintype "bidirectional"))
    )
    (net (code "108") (name "unconnected-(MEGA2560PRO1-PadD49)") (class "Default")
      (node (ref "MEGA2560PRO1") (pin "D49") (pinfunction "D49_D49") (pintype "bidirectional"))
    )
    (net (code "109") (name "unconnected-(MEGA2560PRO1-PadD50)") (class "Default")
      (node (ref "MEGA2560PRO1") (pin "D50") (pinfunction "D50_D50") (pintype "bidirectional"))
    )
    (net (code "110") (name "unconnected-(MEGA2560PRO1-PadD51)") (class "Default")
      (node (ref "MEGA2560PRO1") (pin "D51") (pinfunction "D51_D51") (pintype "bidirectional"))
    )
    (net (code "111") (name "unconnected-(MEGA2560PRO1-PadRST)") (class "Default")
      (node (ref "MEGA2560PRO1") (pin "RST") (pinfunction "RST_RST") (pintype "bidirectional"))
    )
    (net (code "112") (name "unconnected-(MEGA2560PRO1-PadRX)") (class "Default")
      (node (ref "MEGA2560PRO1") (pin "RX") (pinfunction "RX_RX") (pintype "bidirectional"))
    )
    (net (code "113") (name "unconnected-(MEGA2560PRO1-PadTX)") (class "Default")
      (node (ref "MEGA2560PRO1") (pin "TX") (pinfunction "TX_TX") (pintype "bidirectional"))
    )
    (net (code "114") (name "unconnected-(MEGA2560PRO1-VIN-PadVIN@1)") (class "Default")
      (node (ref "MEGA2560PRO1") (pin "VIN@1") (pinfunction "VIN_VIN@1") (pintype "bidirectional"))
    )
    (net (code "115") (name "unconnected-(MEGA2560PRO1-VIN-PadVIN@2)") (class "Default")
      (node (ref "MEGA2560PRO1") (pin "VIN@2") (pinfunction "VIN_VIN@2") (pintype "bidirectional"))
    )
    (net (code "116") (name "unconnected-(PL1-Pad17)") (class "Default")
      (node (ref "PL1") (pin "17") (pinfunction "17_17") (pintype "passive"))
    )
    (net (code "117") (name "unconnected-(U$14-PadCTS)") (class "Default")
      (node (ref "U$14") (pin "CTS") (pinfunction "CTS_CTS") (pintype "bidirectional"))
    )
    (net (code "118") (name "unconnected-(U$14-PadRTS)") (class "Default")
      (node (ref "U$14") (pin "RTS") (pinfunction "RTS_RTS") (pintype "bidirectional"))
    )
    (net (code "119") (name "unconnected-(U$16-Pad3V3)") (class "Default")
      (node (ref "U$16") (pin "3V3") (pinfunction "3V3_3V3") (pintype "bidirectional"))
    )
    (net (code "120") (name "unconnected-(U$16-PadADR)") (class "Default")
      (node (ref "U$16") (pin "ADR") (pinfunction "ADR_ADR") (pintype "bidirectional"))
    )
    (net (code "121") (name "unconnected-(U$16-PadINT)") (class "Default")
      (node (ref "U$16") (pin "INT") (pinfunction "INT_INT") (pintype "bidirectional"))
    )
    (net (code "122") (name "unconnected-(U$16-PadPS0)") (class "Default")
      (node (ref "U$16") (pin "PS0") (pinfunction "PS0_PS0") (pintype "bidirectional"))
    )
    (net (code "123") (name "unconnected-(U$16-PadPS1)") (class "Default")
      (node (ref "U$16") (pin "PS1") (pinfunction "PS1_PS1") (pintype "bidirectional"))
    )
    (net (code "124") (name "unconnected-(U$16-PadRST)") (class "Default")
      (node (ref "U$16") (pin "RST") (pinfunction "RST_RST") (pintype "bidirectional"))
    )
    (net (code "125") (name "unconnected-(U$17-Pad3V3)") (class "Default")
      (node (ref "U$17") (pin "3V3") (pinfunction "3V3_3V3") (pintype "bidirectional"))
    )
    (net (code "126") (name "unconnected-(U$17-PadBOOT)") (class "Default")
      (node (ref "U$17") (pin "BOOT") (pinfunction "BOOT_BOOT") (pintype "bidirectional"))
    )
    (net (code "127") (name "unconnected-(U$17-PadP2)") (class "Default")
      (node (ref "U$17") (pin "P2") (pinfunction "P2_P2") (pintype "bidirectional"))
    )
    (net (code "128") (name "unconnected-(U$17-PadP3)") (class "Default")
      (node (ref "U$17") (pin "P3") (pinfunction "P3_P3") (pintype "bidirectional"))
    )
    (net (code "129") (name "unconnected-(U$17-PadP4)") (class "Default")
      (node (ref "U$17") (pin "P4") (pinfunction "P4_P4") (pintype "bidirectional"))
    )
    (net (code "130") (name "unconnected-(U$17-PadP5)") (class "Default")
      (node (ref "U$17") (pin "P5") (pinfunction "P5_P5") (pintype "bidirectional"))
    )
    (net (code "131") (name "unconnected-(U$17-PadP6)") (class "Default")
      (node (ref "U$17") (pin "P6") (pinfunction "P6_P6") (pintype "bidirectional"))
    )
    (net (code "132") (name "unconnected-(U$17-PadP7)") (class "Default")
      (node (ref "U$17") (pin "P7") (pinfunction "P7_P7") (pintype "bidirectional"))
    )
    (net (code "133") (name "unconnected-(U$17-PadP8)") (class "Default")
      (node (ref "U$17") (pin "P8") (pinfunction "P8_P8") (pintype "bidirectional"))
    )
    (net (code "134") (name "unconnected-(U$17-PadP9)") (class "Default")
      (node (ref "U$17") (pin "P9") (pinfunction "P9_P9") (pintype "bidirectional"))
    )
    (net (code "135") (name "unconnected-(U$17-PadPAD1)") (class "Default")
      (node (ref "U$17") (pin "PAD1") (pinfunction "PAD1_PAD1") (pintype "bidirectional"))
    )
    (net (code "136") (name "unconnected-(U$17-PadPAD2)") (class "Default")
      (node (ref "U$17") (pin "PAD2") (pinfunction "PAD2_PAD2") (pintype "bidirectional"))
    )
    (net (code "137") (name "unconnected-(U$17-PadRST)") (class "Default")
      (node (ref "U$17") (pin "RST") (pinfunction "RST_RST") (pintype "bidirectional"))
    )
    (net (code "138") (name "unconnected-(U$17-PadSYNC)") (class "Default")
      (node (ref "U$17") (pin "SYNC") (pinfunction "SYNC_SYNC") (pintype "bidirectional"))
    )
  )
)
